# nixie_arduino.net
KiCad netlist of a schematic drawn in EAGLE
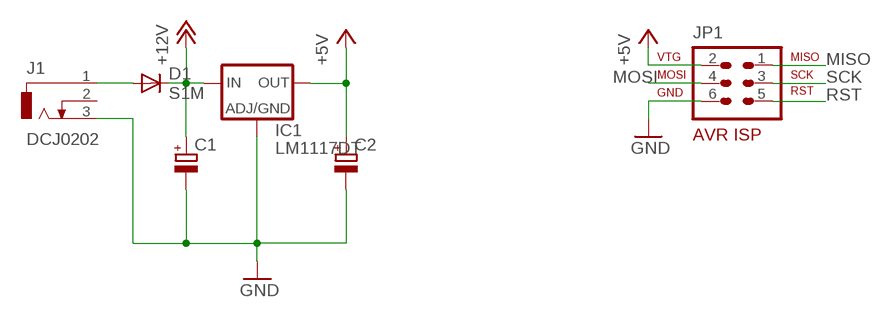
[diagram p0: schematic, sheet 1]

(export (version "E")
  (design (tool "Eeschema 10.0.6"))
  (components
    (comp (ref "C1")
      (value "CPOL-EUD")
      (footprint "eagle-import:PANASONIC_D")
      (libsource (lib "eagle-import") (part "CPOL-EUD"))
    )
    (comp (ref "C2")
      (value "CPOL-EUD")
      (footprint "eagle-import:PANASONIC_D")
      (libsource (lib "eagle-import") (part "CPOL-EUD"))
    )
    (comp (ref "D1")
      (value "S1M")
      (footprint "eagle-import:DO-214AC")
      (libsource (lib "eagle-import") (part "S1M"))
    )
    (comp (ref "IC1")
      (value "LM1117DT")
      (footprint "eagle-import:DPACK")
      (libsource (lib "eagle-import") (part "LM1117DT"))
    )
    (comp (ref "J1")
      (value "DCJ0202")
      (footprint "eagle-import:DCJ0202A")
      (libsource (lib "eagle-import") (part "DCJ0202"))
    )
    (comp (ref "JP1")
      (value "AVR-ISP-6")
      (footprint "eagle-import:AVR-ISP-6")
      (libsource (lib "eagle-import") (part "nixie_tube_AVR-ISP-6"))
    )
  )
  (nets
    (net (code "1") (name "+5V") (class "Default")
      (node (ref "C2") (pin "+") (pinfunction "+_+") (pintype "passive"))
      (node (ref "IC1") (pin "4") (pinfunction "OUT_4") (pintype "passive"))
      (node (ref "JP1") (pin "2") (pinfunction "VTG_2") (pintype "passive"))
    )
    (net (code "2") (name "+12V") (class "Default")
      (node (ref "C1") (pin "+") (pinfunction "+_+") (pintype "passive"))
      (node (ref "D1") (pin "C") (pinfunction "C_C") (pintype "passive"))
      (node (ref "IC1") (pin "3") (pinfunction "IN_3") (pintype "input"))
    )
    (net (code "3") (name "/MISO") (class "Default")
      (node (ref "JP1") (pin "1") (pinfunction "MISO_1") (pintype "passive"))
    )
    (net (code "4") (name "/MOSI") (class "Default")
      (node (ref "JP1") (pin "4") (pinfunction "MOSI_4") (pintype "passive"))
    )
    (net (code "5") (name "/RST") (class "Default")
      (node (ref "JP1") (pin "5") (pinfunction "RST_5") (pintype "passive"))
    )
    (net (code "6") (name "/SCK") (class "Default")
      (node (ref "JP1") (pin "3") (pinfunction "SCK_3") (pintype "passive"))
    )
    (net (code "7") (name "GND") (class "Default")
      (node (ref "C1") (pin "-") (pinfunction "-_-") (pintype "passive"))
      (node (ref "C2") (pin "-") (pinfunction "-_-") (pintype "passive"))
      (node (ref "IC1") (pin "1") (pinfunction "ADJ_1") (pintype "input"))
      (node (ref "J1") (pin "3") (pinfunction "3_3") (pintype "passive"))
      (node (ref "JP1") (pin "6") (pinfunction "GND_6") (pintype "passive"))
    )
    (net (code "8") (name "Net-(D1-PadA)") (class "Default")
      (node (ref "D1") (pin "A") (pinfunction "A_A") (pintype "passive"))
      (node (ref "J1") (pin "1") (pinfunction "1_1") (pintype "passive"))
    )
    (net (code "9") (name "unconnected-(J1-Pad2)") (class "Default")
      (node (ref "J1") (pin "2") (pinfunction "2_2") (pintype "passive"))
    )
  )
)
